# esp8266_aquarium_light.net
KiCad netlist of a schematic drawn in EAGLE
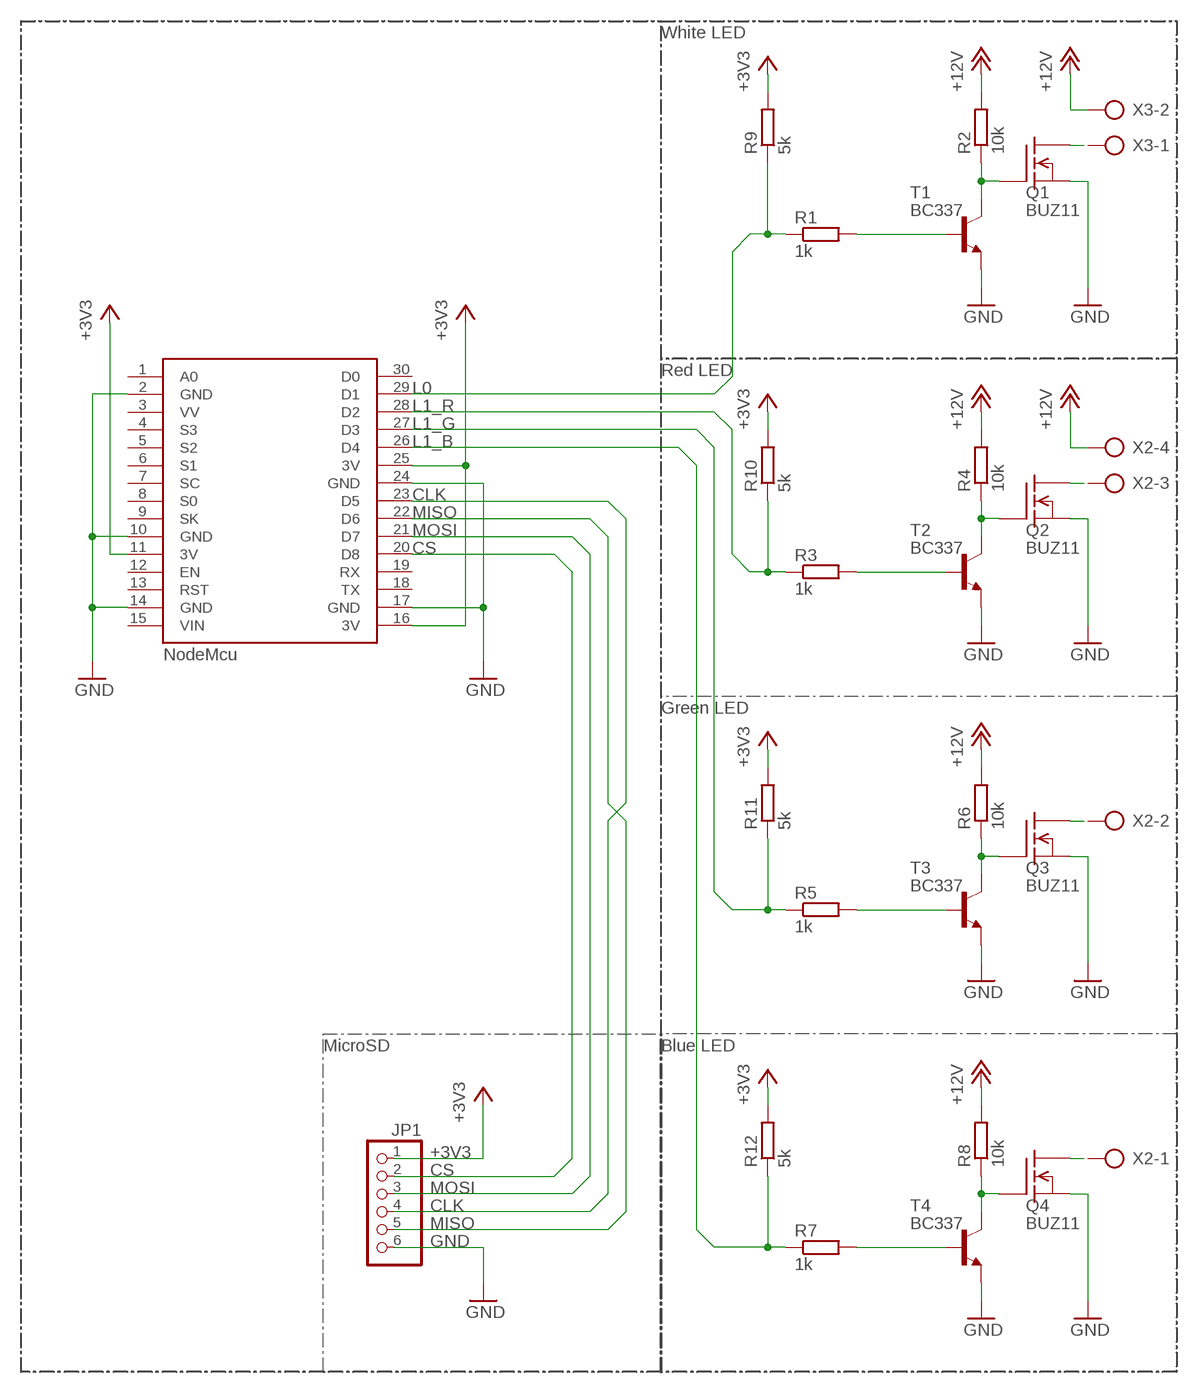
[diagram p0: schematic, sheet 1]

(export (version "E")
  (design (tool "Eeschema 10.0.6"))
  (components
    (comp (ref "JP1")
      (value "PINHD-1X6")
      (footprint "eagle-import:1X06")
      (libsource (lib "eagle-import") (part "PINHD-1X6"))
    )
    (comp (ref "Q1")
      (value "BUZ11")
      (footprint "eagle-import:TO220")
      (libsource (lib "eagle-import") (part "BUZ11"))
    )
    (comp (ref "Q2")
      (value "BUZ11")
      (footprint "eagle-import:TO220")
      (libsource (lib "eagle-import") (part "BUZ11"))
    )
    (comp (ref "Q3")
      (value "BUZ11")
      (footprint "eagle-import:TO220")
      (libsource (lib "eagle-import") (part "BUZ11"))
    )
    (comp (ref "Q4")
      (value "BUZ11")
      (footprint "eagle-import:TO220")
      (libsource (lib "eagle-import") (part "BUZ11"))
    )
    (comp (ref "R1")
      (value "1k")
      (footprint "eagle-import:0309_12")
      (libsource (lib "eagle-import") (part "R-EU_0309/12"))
    )
    (comp (ref "R2")
      (value "10k")
      (footprint "eagle-import:0309_12")
      (libsource (lib "eagle-import") (part "R-EU_0309/12"))
    )
    (comp (ref "R3")
      (value "1k")
      (footprint "eagle-import:0309_12")
      (libsource (lib "eagle-import") (part "R-EU_0309/12"))
    )
    (comp (ref "R4")
      (value "10k")
      (footprint "eagle-import:0309_12")
      (libsource (lib "eagle-import") (part "R-EU_0309/12"))
    )
    (comp (ref "R5")
      (value "1k")
      (footprint "eagle-import:0309_12")
      (libsource (lib "eagle-import") (part "R-EU_0309/12"))
    )
    (comp (ref "R6")
      (value "10k")
      (footprint "eagle-import:0309_12")
      (libsource (lib "eagle-import") (part "R-EU_0309/12"))
    )
    (comp (ref "R7")
      (value "1k")
      (footprint "eagle-import:0309_12")
      (libsource (lib "eagle-import") (part "R-EU_0309/12"))
    )
    (comp (ref "R8")
      (value "10k")
      (footprint "eagle-import:0309_12")
      (libsource (lib "eagle-import") (part "R-EU_0309/12"))
    )
    (comp (ref "R9")
      (value "5k")
      (footprint "eagle-import:0309_12")
      (libsource (lib "eagle-import") (part "R-EU_0309/12"))
    )
    (comp (ref "R10")
      (value "5k")
      (footprint "eagle-import:0309_12")
      (libsource (lib "eagle-import") (part "R-EU_0309/12"))
    )
    (comp (ref "R11")
      (value "5k")
      (footprint "eagle-import:0309_12")
      (libsource (lib "eagle-import") (part "R-EU_0309/12"))
    )
    (comp (ref "R12")
      (value "5k")
      (footprint "eagle-import:0309_12")
      (libsource (lib "eagle-import") (part "R-EU_0309/12"))
    )
    (comp (ref "T1")
      (value "BC337")
      (footprint "eagle-import:TO92")
      (libsource (lib "eagle-import") (part "BC337"))
    )
    (comp (ref "T2")
      (value "BC337")
      (footprint "eagle-import:TO92")
      (libsource (lib "eagle-import") (part "BC337"))
    )
    (comp (ref "T3")
      (value "BC337")
      (footprint "eagle-import:TO92")
      (libsource (lib "eagle-import") (part "BC337"))
    )
    (comp (ref "T4")
      (value "BC337")
      (footprint "eagle-import:TO92")
      (libsource (lib "eagle-import") (part "BC337"))
    )
    (comp (ref "U$1")
      (value "NODEMCU")
      (footprint "eagle-import:NODEMCU")
      (libsource (lib "eagle-import") (part "NODEMCU"))
    )
    (comp (ref "X2")
      (value "AK500/4")
      (footprint "eagle-import:AK500_4")
      (libsource (lib "eagle-import") (part "AK500/4"))
    )
    (comp (ref "X3")
      (value "AK500/2")
      (footprint "eagle-import:AK500_2")
      (libsource (lib "eagle-import") (part "AK500/2"))
    )
  )
  (nets
    (net (code "1") (name "+3V3") (class "Default")
      (node (ref "JP1") (pin "1") (pinfunction "1_1") (pintype "passive"))
      (node (ref "R10") (pin "2") (pinfunction "2_2") (pintype "passive"))
      (node (ref "R11") (pin "2") (pinfunction "2_2") (pintype "passive"))
      (node (ref "R12") (pin "2") (pinfunction "2_2") (pintype "passive"))
      (node (ref "R9") (pin "2") (pinfunction "2_2") (pintype "passive"))
      (node (ref "U$1") (pin "11") (pinfunction "3V_11") (pintype "power_in"))
      (node (ref "U$1") (pin "16") (pinfunction "3V_16") (pintype "power_in"))
      (node (ref "U$1") (pin "25") (pinfunction "3V_25") (pintype "power_in"))
    )
    (net (code "2") (name "+12V") (class "Default")
      (node (ref "R2") (pin "2") (pinfunction "2_2") (pintype "passive"))
      (node (ref "R4") (pin "2") (pinfunction "2_2") (pintype "passive"))
      (node (ref "R6") (pin "2") (pinfunction "2_2") (pintype "passive"))
      (node (ref "R8") (pin "2") (pinfunction "2_2") (pintype "passive"))
      (node (ref "X2") (pin "4") (pinfunction "KL_4") (pintype "passive"))
      (node (ref "X3") (pin "2") (pinfunction "KL_2") (pintype "passive"))
    )
    (net (code "3") (name "/CLK") (class "Default")
      (node (ref "JP1") (pin "4") (pinfunction "4_4") (pintype "passive"))
      (node (ref "U$1") (pin "23") (pinfunction "D5_23") (pintype "bidirectional"))
    )
    (net (code "4") (name "/CS") (class "Default")
      (node (ref "JP1") (pin "2") (pinfunction "2_2") (pintype "passive"))
      (node (ref "U$1") (pin "20") (pinfunction "D8_20") (pintype "bidirectional"))
    )
    (net (code "5") (name "/L0") (class "Default")
      (node (ref "R1") (pin "1") (pinfunction "1_1") (pintype "passive"))
      (node (ref "R9") (pin "1") (pinfunction "1_1") (pintype "passive"))
      (node (ref "U$1") (pin "29") (pinfunction "D1_29") (pintype "bidirectional"))
    )
    (net (code "6") (name "/L1_B") (class "Default")
      (node (ref "R12") (pin "1") (pinfunction "1_1") (pintype "passive"))
      (node (ref "R7") (pin "1") (pinfunction "1_1") (pintype "passive"))
      (node (ref "U$1") (pin "26") (pinfunction "D4_26") (pintype "bidirectional"))
    )
    (net (code "7") (name "/L1_G") (class "Default")
      (node (ref "R11") (pin "1") (pinfunction "1_1") (pintype "passive"))
      (node (ref "R5") (pin "1") (pinfunction "1_1") (pintype "passive"))
      (node (ref "U$1") (pin "27") (pinfunction "D3_27") (pintype "bidirectional"))
    )
    (net (code "8") (name "/L1_R") (class "Default")
      (node (ref "R10") (pin "1") (pinfunction "1_1") (pintype "passive"))
      (node (ref "R3") (pin "1") (pinfunction "1_1") (pintype "passive"))
      (node (ref "U$1") (pin "28") (pinfunction "D2_28") (pintype "bidirectional"))
    )
    (net (code "9") (name "/MISO") (class "Default")
      (node (ref "JP1") (pin "5") (pinfunction "5_5") (pintype "passive"))
      (node (ref "U$1") (pin "22") (pinfunction "D6_22") (pintype "bidirectional"))
    )
    (net (code "10") (name "/MOSI") (class "Default")
      (node (ref "JP1") (pin "3") (pinfunction "3_3") (pintype "passive"))
      (node (ref "U$1") (pin "21") (pinfunction "D7_21") (pintype "bidirectional"))
    )
    (net (code "11") (name "GND") (class "Default")
      (node (ref "JP1") (pin "6") (pinfunction "6_6") (pintype "passive"))
      (node (ref "Q1") (pin "3") (pinfunction "S_3") (pintype "passive"))
      (node (ref "Q2") (pin "3") (pinfunction "S_3") (pintype "passive"))
      (node (ref "Q3") (pin "3") (pinfunction "S_3") (pintype "passive"))
      (node (ref "Q4") (pin "3") (pinfunction "S_3") (pintype "passive"))
      (node (ref "T1") (pin "1") (pinfunction "E_1") (pintype "passive"))
      (node (ref "T2") (pin "1") (pinfunction "E_1") (pintype "passive"))
      (node (ref "T3") (pin "1") (pinfunction "E_1") (pintype "passive"))
      (node (ref "T4") (pin "1") (pinfunction "E_1") (pintype "passive"))
      (node (ref "U$1") (pin "10") (pinfunction "GND_10") (pintype "power_in"))
      (node (ref "U$1") (pin "14") (pinfunction "GND_14") (pintype "power_in"))
      (node (ref "U$1") (pin "17") (pinfunction "GND_17") (pintype "power_in"))
      (node (ref "U$1") (pin "2") (pinfunction "GND_2") (pintype "power_in"))
      (node (ref "U$1") (pin "24") (pinfunction "GND_24") (pintype "power_in"))
    )
    (net (code "12") (name "Net-(Q1-D)") (class "Default")
      (node (ref "Q1") (pin "2") (pinfunction "D_2") (pintype "passive"))
      (node (ref "X3") (pin "1") (pinfunction "KL_1") (pintype "passive"))
    )
    (net (code "13") (name "Net-(Q1-G)") (class "Default")
      (node (ref "Q1") (pin "1") (pinfunction "G_1") (pintype "passive"))
      (node (ref "R2") (pin "1") (pinfunction "1_1") (pintype "passive"))
      (node (ref "T1") (pin "3") (pinfunction "C_3") (pintype "passive"))
    )
    (net (code "14") (name "Net-(Q2-D)") (class "Default")
      (node (ref "Q2") (pin "2") (pinfunction "D_2") (pintype "passive"))
      (node (ref "X2") (pin "3") (pinfunction "KL_3") (pintype "passive"))
    )
    (net (code "15") (name "Net-(Q2-G)") (class "Default")
      (node (ref "Q2") (pin "1") (pinfunction "G_1") (pintype "passive"))
      (node (ref "R4") (pin "1") (pinfunction "1_1") (pintype "passive"))
      (node (ref "T2") (pin "3") (pinfunction "C_3") (pintype "passive"))
    )
    (net (code "16") (name "Net-(Q3-D)") (class "Default")
      (node (ref "Q3") (pin "2") (pinfunction "D_2") (pintype "passive"))
      (node (ref "X2") (pin "2") (pinfunction "KL_2") (pintype "passive"))
    )
    (net (code "17") (name "Net-(Q3-G)") (class "Default")
      (node (ref "Q3") (pin "1") (pinfunction "G_1") (pintype "passive"))
      (node (ref "R6") (pin "1") (pinfunction "1_1") (pintype "passive"))
      (node (ref "T3") (pin "3") (pinfunction "C_3") (pintype "passive"))
    )
    (net (code "18") (name "Net-(Q4-D)") (class "Default")
      (node (ref "Q4") (pin "2") (pinfunction "D_2") (pintype "passive"))
      (node (ref "X2") (pin "1") (pinfunction "KL_1") (pintype "passive"))
    )
    (net (code "19") (name "Net-(Q4-G)") (class "Default")
      (node (ref "Q4") (pin "1") (pinfunction "G_1") (pintype "passive"))
      (node (ref "R8") (pin "1") (pinfunction "1_1") (pintype "passive"))
      (node (ref "T4") (pin "3") (pinfunction "C_3") (pintype "passive"))
    )
    (net (code "20") (name "Net-(T1-B)") (class "Default")
      (node (ref "R1") (pin "2") (pinfunction "2_2") (pintype "passive"))
      (node (ref "T1") (pin "2") (pinfunction "B_2") (pintype "passive"))
    )
    (net (code "21") (name "Net-(T2-B)") (class "Default")
      (node (ref "R3") (pin "2") (pinfunction "2_2") (pintype "passive"))
      (node (ref "T2") (pin "2") (pinfunction "B_2") (pintype "passive"))
    )
    (net (code "22") (name "Net-(T3-B)") (class "Default")
      (node (ref "R5") (pin "2") (pinfunction "2_2") (pintype "passive"))
      (node (ref "T3") (pin "2") (pinfunction "B_2") (pintype "passive"))
    )
    (net (code "23") (name "Net-(T4-B)") (class "Default")
      (node (ref "R7") (pin "2") (pinfunction "2_2") (pintype "passive"))
      (node (ref "T4") (pin "2") (pinfunction "B_2") (pintype "passive"))
    )
    (net (code "24") (name "unconnected-(U$1-A0-Pad1)") (class "Default")
      (node (ref "U$1") (pin "1") (pinfunction "A0_1") (pintype "bidirectional"))
    )
    (net (code "25") (name "unconnected-(U$1-D0-Pad30)") (class "Default")
      (node (ref "U$1") (pin "30") (pinfunction "D0_30") (pintype "bidirectional"))
    )
    (net (code "26") (name "unconnected-(U$1-EN-Pad12)") (class "Default")
      (node (ref "U$1") (pin "12") (pinfunction "EN_12") (pintype "bidirectional"))
    )
    (net (code "27") (name "unconnected-(U$1-RST-Pad13)") (class "Default")
      (node (ref "U$1") (pin "13") (pinfunction "RST_13") (pintype "bidirectional"))
    )
    (net (code "28") (name "unconnected-(U$1-RX-Pad19)") (class "Default")
      (node (ref "U$1") (pin "19") (pinfunction "RX_19") (pintype "bidirectional"))
    )
    (net (code "29") (name "unconnected-(U$1-S0-Pad8)") (class "Default")
      (node (ref "U$1") (pin "8") (pinfunction "S0_8") (pintype "bidirectional"))
    )
    (net (code "30") (name "unconnected-(U$1-S1-Pad6)") (class "Default")
      (node (ref "U$1") (pin "6") (pinfunction "S1_6") (pintype "bidirectional"))
    )
    (net (code "31") (name "unconnected-(U$1-S2-Pad5)") (class "Default")
      (node (ref "U$1") (pin "5") (pinfunction "S2_5") (pintype "bidirectional"))
    )
    (net (code "32") (name "unconnected-(U$1-S3-Pad4)") (class "Default")
      (node (ref "U$1") (pin "4") (pinfunction "S3_4") (pintype "bidirectional"))
    )
    (net (code "33") (name "unconnected-(U$1-SC-Pad7)") (class "Default")
      (node (ref "U$1") (pin "7") (pinfunction "SC_7") (pintype "bidirectional"))
    )
    (net (code "34") (name "unconnected-(U$1-SK-Pad9)") (class "Default")
      (node (ref "U$1") (pin "9") (pinfunction "SK_9") (pintype "bidirectional"))
    )
    (net (code "35") (name "unconnected-(U$1-TX-Pad18)") (class "Default")
      (node (ref "U$1") (pin "18") (pinfunction "TX_18") (pintype "bidirectional"))
    )
    (net (code "36") (name "unconnected-(U$1-VIN-Pad15)") (class "Default")
      (node (ref "U$1") (pin "15") (pinfunction "VIN_15") (pintype "bidirectional"))
    )
    (net (code "37") (name "unconnected-(U$1-VV-Pad3)") (class "Default")
      (node (ref "U$1") (pin "3") (pinfunction "VV_3") (pintype "bidirectional"))
    )
  )
)
